# PixiFlood_SMT.net
KiCad netlist of a schematic drawn in EAGLE
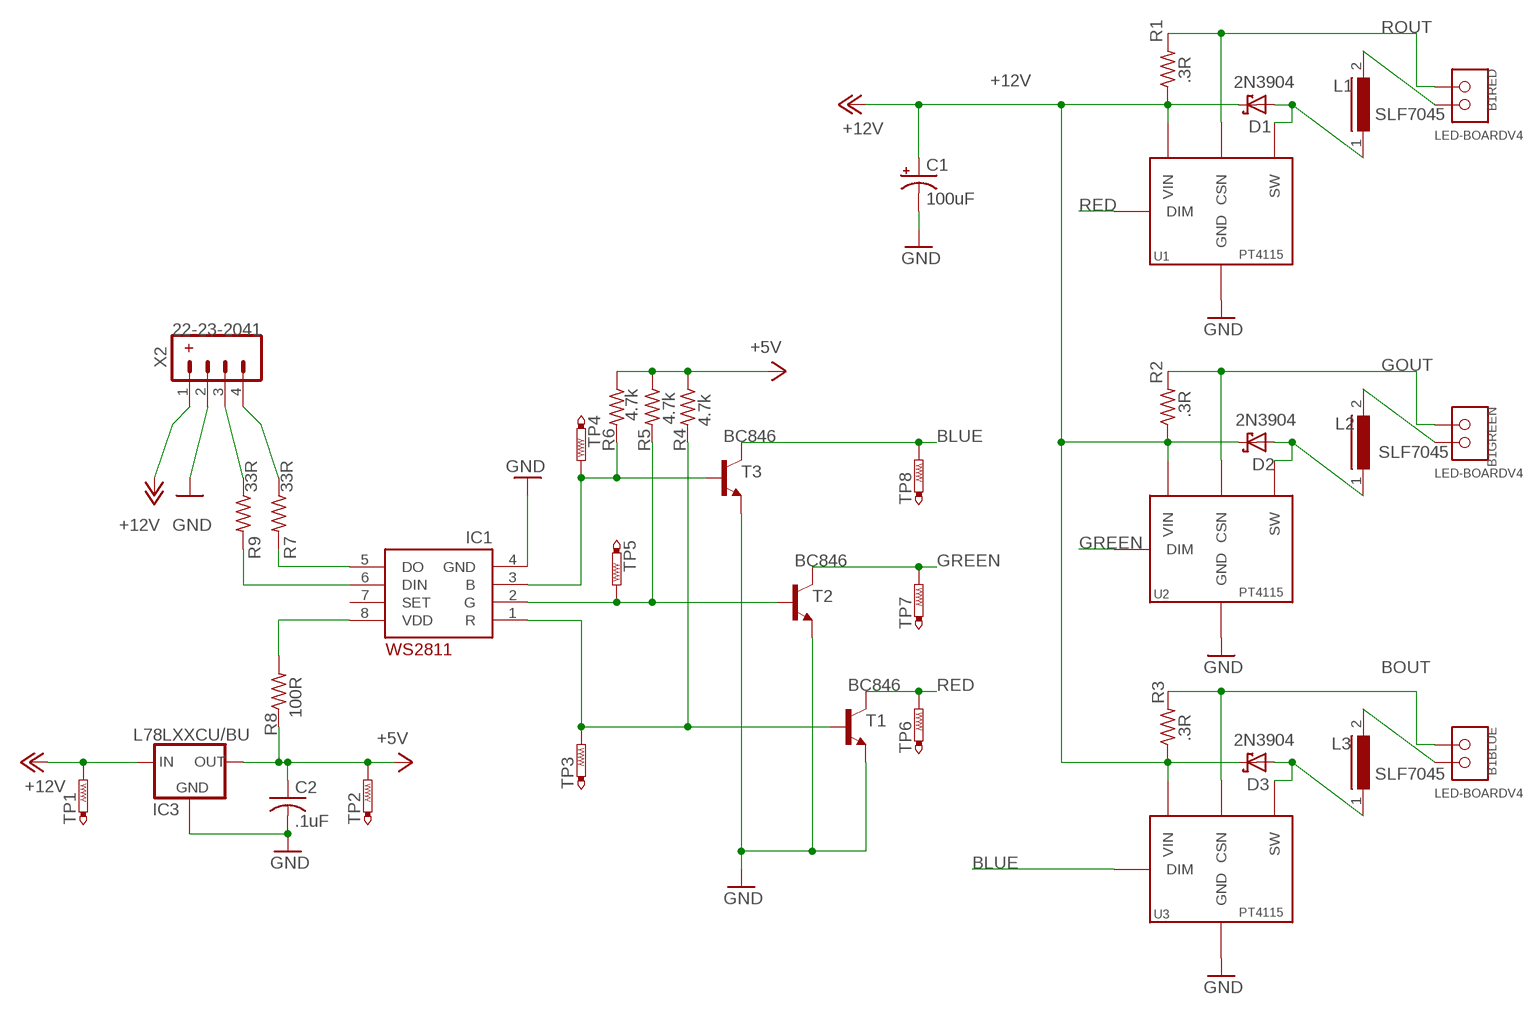
[diagram p0: schematic, sheet 1]

(export (version "E")
  (design (tool "Eeschema 10.0.6"))
  (components
    (comp (ref "B1")
      (value "LED-BOARDV4")
      (footprint "eagle-import:LED_BOARD-V4")
      (libsource (lib "eagle-import") (part "LED-BOARDV4"))
    )
    (comp (ref "C1")
      (value "100uF")
      (footprint "eagle-import:TT2D6L")
      (libsource (lib "eagle-import") (part "CPOL-USTT2D6L"))
    )
    (comp (ref "C2")
      (value ".1uF")
      (footprint "eagle-import:C0805")
      (libsource (lib "eagle-import") (part "C-USC0805"))
    )
    (comp (ref "D1")
      (value "2N3904")
      (footprint "eagle-import:SMA-DO214AC")
      (libsource (lib "eagle-import") (part "SCHOTTKY-DIODESS16"))
    )
    (comp (ref "D2")
      (value "2N3904")
      (footprint "eagle-import:SMA-DO214AC")
      (libsource (lib "eagle-import") (part "SCHOTTKY-DIODESS16"))
    )
    (comp (ref "D3")
      (value "2N3904")
      (footprint "eagle-import:SMA-DO214AC")
      (libsource (lib "eagle-import") (part "SCHOTTKY-DIODESS16"))
    )
    (comp (ref "IC1")
      (value "WS2811-SOP8")
      (footprint "eagle-import:SO08-SKINNYPADS")
      (libsource (lib "eagle-import") (part "WS2811-SOP8"))
    )
    (comp (ref "IC3")
      (value "L78LXXCU/BU")
      (footprint "eagle-import:SOT89")
      (libsource (lib "eagle-import") (part "L78LXXCU/BU"))
    )
    (comp (ref "L1")
      (value "SLF7045")
      (footprint "eagle-import:SLF7045")
      (libsource (lib "eagle-import") (part "SLF7045"))
    )
    (comp (ref "L2")
      (value "SLF7045")
      (footprint "eagle-import:SLF7045")
      (libsource (lib "eagle-import") (part "SLF7045"))
    )
    (comp (ref "L3")
      (value "SLF7045")
      (footprint "eagle-import:SLF7045")
      (libsource (lib "eagle-import") (part "SLF7045"))
    )
    (comp (ref "R1")
      (value ".3R")
      (footprint "eagle-import:R1206")
      (libsource (lib "eagle-import") (part "resistor_R-US_R1206"))
    )
    (comp (ref "R2")
      (value ".3R")
      (footprint "eagle-import:R1206")
      (libsource (lib "eagle-import") (part "resistor_R-US_R1206"))
    )
    (comp (ref "R3")
      (value ".3R")
      (footprint "eagle-import:R1206")
      (libsource (lib "eagle-import") (part "resistor_R-US_R1206"))
    )
    (comp (ref "R4")
      (value "4.7k")
      (footprint "eagle-import:R0805")
      (libsource (lib "eagle-import") (part "resistor_R-US_R0805"))
    )
    (comp (ref "R5")
      (value "4.7k")
      (footprint "eagle-import:R0805")
      (libsource (lib "eagle-import") (part "resistor_R-US_R0805"))
    )
    (comp (ref "R6")
      (value "4.7k")
      (footprint "eagle-import:R0805")
      (libsource (lib "eagle-import") (part "resistor_R-US_R0805"))
    )
    (comp (ref "R7")
      (value "33R")
      (footprint "eagle-import:M0805")
      (libsource (lib "eagle-import") (part "R-US_M0805"))
    )
    (comp (ref "R8")
      (value "100R")
      (footprint "eagle-import:R0805")
      (libsource (lib "eagle-import") (part "R-US_R0805"))
    )
    (comp (ref "R9")
      (value "33R")
      (footprint "eagle-import:R0805")
      (libsource (lib "eagle-import") (part "R-US_R0805"))
    )
    (comp (ref "T1")
      (value "BC846")
      (footprint "eagle-import:SOT23")
      (libsource (lib "eagle-import") (part "BC846"))
    )
    (comp (ref "T2")
      (value "BC846")
      (footprint "eagle-import:SOT23")
      (libsource (lib "eagle-import") (part "BC846"))
    )
    (comp (ref "T3")
      (value "BC846")
      (footprint "eagle-import:SOT23")
      (libsource (lib "eagle-import") (part "BC846"))
    )
    (comp (ref "TP1")
      (value "PTR1TP20SQ")
      (footprint "eagle-import:TP20SQ")
      (libsource (lib "eagle-import") (part "PTR1TP20SQ"))
    )
    (comp (ref "TP2")
      (value "PTR1TP20R")
      (footprint "eagle-import:TP20R")
      (libsource (lib "eagle-import") (part "PTR1TP20R"))
    )
    (comp (ref "TP3")
      (value "PTR1B1,27")
      (footprint "eagle-import:B1,27")
      (libsource (lib "eagle-import") (part "PTR1B1,27"))
    )
    (comp (ref "TP4")
      (value "PTR1B1,27")
      (footprint "eagle-import:B1,27")
      (libsource (lib "eagle-import") (part "PTR1B1,27"))
    )
    (comp (ref "TP5")
      (value "PTR1B1,27")
      (footprint "eagle-import:B1,27")
      (libsource (lib "eagle-import") (part "PTR1B1,27"))
    )
    (comp (ref "TP6")
      (value "PTR1B1,27")
      (footprint "eagle-import:B1,27")
      (libsource (lib "eagle-import") (part "PTR1B1,27"))
    )
    (comp (ref "TP7")
      (value "PTR1B1,27")
      (footprint "eagle-import:B1,27")
      (libsource (lib "eagle-import") (part "PTR1B1,27"))
    )
    (comp (ref "TP8")
      (value "PTR1B1,27")
      (footprint "eagle-import:B1,27")
      (libsource (lib "eagle-import") (part "PTR1B1,27"))
    )
    (comp (ref "U1")
      (value "PT4115B89E")
      (footprint "eagle-import:SOT89-5")
      (libsource (lib "eagle-import") (part "PT4115B89E"))
    )
    (comp (ref "U2")
      (value "PT4115B89E")
      (footprint "eagle-import:SOT89-5")
      (libsource (lib "eagle-import") (part "PT4115B89E"))
    )
    (comp (ref "U3")
      (value "PT4115B89E")
      (footprint "eagle-import:SOT89-5")
      (libsource (lib "eagle-import") (part "PT4115B89E"))
    )
    (comp (ref "X2")
      (value "22-23-2041")
      (footprint "eagle-import:22-23-2041")
      (fields (field (name "MF") "MOLEX"))
      (libsource (lib "eagle-import") (part "22-23-2041"))
    )
  )
  (nets
    (net (code "1") (name "+5V") (class "Default")
      (node (ref "C2") (pin "1") (pinfunction "1_1") (pintype "passive"))
      (node (ref "IC3") (pin "1") (pinfunction "OUT_1") (pintype "passive"))
      (node (ref "R4") (pin "1") (pinfunction "1_1") (pintype "passive"))
      (node (ref "R5") (pin "1") (pinfunction "1_1") (pintype "passive"))
      (node (ref "R6") (pin "1") (pinfunction "1_1") (pintype "passive"))
      (node (ref "R8") (pin "1") (pinfunction "1_1") (pintype "passive"))
      (node (ref "TP2") (pin "TP") (pinfunction "TP_TP") (pintype "input"))
    )
    (net (code "2") (name "+12V") (class "Default")
      (node (ref "C1") (pin "+") (pinfunction "+_+") (pintype "passive"))
      (node (ref "D1") (pin "K") (pinfunction "C_K") (pintype "passive"))
      (node (ref "D2") (pin "K") (pinfunction "C_K") (pintype "passive"))
      (node (ref "D3") (pin "K") (pinfunction "C_K") (pintype "passive"))
      (node (ref "IC3") (pin "3") (pinfunction "IN_3") (pintype "input"))
      (node (ref "R1") (pin "1") (pinfunction "1_1") (pintype "passive"))
      (node (ref "R2") (pin "1") (pinfunction "1_1") (pintype "passive"))
      (node (ref "R3") (pin "1") (pinfunction "1_1") (pintype "passive"))
      (node (ref "TP1") (pin "TP") (pinfunction "TP_TP") (pintype "input"))
      (node (ref "U1") (pin "5") (pinfunction "VIN_5") (pintype "power_in"))
      (node (ref "U2") (pin "5") (pinfunction "VIN_5") (pintype "power_in"))
      (node (ref "U3") (pin "5") (pinfunction "VIN_5") (pintype "power_in"))
      (node (ref "X2") (pin "1") (pinfunction "1_1") (pintype "passive"))
    )
    (net (code "3") (name "/BLUE") (class "Default")
      (node (ref "T3") (pin "3") (pinfunction "C_3") (pintype "passive"))
      (node (ref "TP8") (pin "TP") (pinfunction "TP_TP") (pintype "input"))
      (node (ref "U3") (pin "3") (pinfunction "DIM_3") (pintype "bidirectional"))
    )
    (net (code "4") (name "/BOUT") (class "Default")
      (node (ref "B1") (pin "B+") (pinfunction "P$2_B+") (pintype "bidirectional"))
      (node (ref "B1") (pin "B+@2") (pinfunction "P$2_B+@2") (pintype "bidirectional"))
      (node (ref "R3") (pin "2") (pinfunction "2_2") (pintype "passive"))
      (node (ref "U3") (pin "4") (pinfunction "CSN_4") (pintype "bidirectional"))
    )
    (net (code "5") (name "/GOUT") (class "Default")
      (node (ref "B1") (pin "G+") (pinfunction "P$2_G+") (pintype "bidirectional"))
      (node (ref "B1") (pin "G+@1") (pinfunction "P$2_G+@1") (pintype "bidirectional"))
      (node (ref "R2") (pin "2") (pinfunction "2_2") (pintype "passive"))
      (node (ref "U2") (pin "4") (pinfunction "CSN_4") (pintype "bidirectional"))
    )
    (net (code "6") (name "/GREEN") (class "Default")
      (node (ref "T2") (pin "3") (pinfunction "C_3") (pintype "passive"))
      (node (ref "TP7") (pin "TP") (pinfunction "TP_TP") (pintype "input"))
      (node (ref "U2") (pin "3") (pinfunction "DIM_3") (pintype "bidirectional"))
    )
    (net (code "7") (name "/RED") (class "Default")
      (node (ref "T1") (pin "3") (pinfunction "C_3") (pintype "passive"))
      (node (ref "TP6") (pin "TP") (pinfunction "TP_TP") (pintype "input"))
      (node (ref "U1") (pin "3") (pinfunction "DIM_3") (pintype "bidirectional"))
    )
    (net (code "8") (name "/ROUT") (class "Default")
      (node (ref "B1") (pin "R+") (pinfunction "P$2_R+") (pintype "bidirectional"))
      (node (ref "B1") (pin "R+@1") (pinfunction "P$2_R+@1") (pintype "bidirectional"))
      (node (ref "R1") (pin "2") (pinfunction "2_2") (pintype "passive"))
      (node (ref "U1") (pin "4") (pinfunction "CSN_4") (pintype "bidirectional"))
    )
    (net (code "9") (name "GND") (class "Default")
      (node (ref "C1") (pin "-") (pinfunction "-_-") (pintype "passive"))
      (node (ref "C2") (pin "2") (pinfunction "2_2") (pintype "passive"))
      (node (ref "IC1") (pin "4") (pinfunction "GND_4") (pintype "power_in"))
      (node (ref "IC3") (pin "4") (pinfunction "GND1_4") (pintype "input"))
      (node (ref "T1") (pin "2") (pinfunction "E_2") (pintype "passive"))
      (node (ref "T2") (pin "2") (pinfunction "E_2") (pintype "passive"))
      (node (ref "T3") (pin "2") (pinfunction "E_2") (pintype "passive"))
      (node (ref "U1") (pin "2") (pinfunction "GND_2") (pintype "power_in"))
      (node (ref "U1") (pin "2@1") (pinfunction "GND_2@1") (pintype "power_in"))
      (node (ref "U1") (pin "2@2") (pinfunction "GND_2@2") (pintype "power_in"))
      (node (ref "U1") (pin "2@3") (pinfunction "GND_2@3") (pintype "power_in"))
      (node (ref "U2") (pin "2") (pinfunction "GND_2") (pintype "power_in"))
      (node (ref "U2") (pin "2@1") (pinfunction "GND_2@1") (pintype "power_in"))
      (node (ref "U2") (pin "2@2") (pinfunction "GND_2@2") (pintype "power_in"))
      (node (ref "U2") (pin "2@3") (pinfunction "GND_2@3") (pintype "power_in"))
      (node (ref "U3") (pin "2") (pinfunction "GND_2") (pintype "power_in"))
      (node (ref "U3") (pin "2@1") (pinfunction "GND_2@1") (pintype "power_in"))
      (node (ref "U3") (pin "2@2") (pinfunction "GND_2@2") (pintype "power_in"))
      (node (ref "U3") (pin "2@3") (pinfunction "GND_2@3") (pintype "power_in"))
      (node (ref "X2") (pin "2") (pinfunction "2_2") (pintype "passive"))
    )
    (net (code "10") (name "Net-(B1A-P$1-PadB-)") (class "Default")
      (node (ref "B1") (pin "B-") (pinfunction "P$1_B-") (pintype "bidirectional"))
      (node (ref "B1") (pin "B-@1") (pinfunction "P$1_B-@1") (pintype "bidirectional"))
      (node (ref "L3") (pin "2") (pinfunction "2_2") (pintype "passive"))
    )
    (net (code "11") (name "Net-(B1B-P$1-PadG-)") (class "Default")
      (node (ref "B1") (pin "G-") (pinfunction "P$1_G-") (pintype "bidirectional"))
      (node (ref "B1") (pin "G-@1") (pinfunction "P$1_G-@1") (pintype "bidirectional"))
      (node (ref "L2") (pin "2") (pinfunction "2_2") (pintype "passive"))
    )
    (net (code "12") (name "Net-(B1C-P$1-PadR-)") (class "Default")
      (node (ref "B1") (pin "R-") (pinfunction "P$1_R-") (pintype "bidirectional"))
      (node (ref "B1") (pin "R-@1") (pinfunction "P$1_R-@1") (pintype "bidirectional"))
      (node (ref "L1") (pin "2") (pinfunction "2_2") (pintype "passive"))
    )
    (net (code "13") (name "Net-(IC1-B)") (class "Default")
      (node (ref "IC1") (pin "3") (pinfunction "B_3") (pintype "open_collector"))
      (node (ref "R6") (pin "2") (pinfunction "2_2") (pintype "passive"))
      (node (ref "T3") (pin "1") (pinfunction "B_1") (pintype "passive"))
      (node (ref "TP4") (pin "TP") (pinfunction "TP_TP") (pintype "input"))
    )
    (net (code "14") (name "Net-(IC1-DIN)") (class "Default")
      (node (ref "IC1") (pin "6") (pinfunction "DIN_6") (pintype "input"))
      (node (ref "R9") (pin "2") (pinfunction "2_2") (pintype "passive"))
    )
    (net (code "15") (name "Net-(IC1-DO)") (class "Default")
      (node (ref "IC1") (pin "5") (pinfunction "DO_5") (pintype "output"))
      (node (ref "R7") (pin "2") (pinfunction "2_2") (pintype "passive"))
    )
    (net (code "16") (name "Net-(IC1-G)") (class "Default")
      (node (ref "IC1") (pin "2") (pinfunction "G_2") (pintype "open_collector"))
      (node (ref "R5") (pin "2") (pinfunction "2_2") (pintype "passive"))
      (node (ref "T2") (pin "1") (pinfunction "B_1") (pintype "passive"))
      (node (ref "TP5") (pin "TP") (pinfunction "TP_TP") (pintype "input"))
    )
    (net (code "17") (name "Net-(IC1-R)") (class "Default")
      (node (ref "IC1") (pin "1") (pinfunction "R_1") (pintype "open_collector"))
      (node (ref "R4") (pin "2") (pinfunction "2_2") (pintype "passive"))
      (node (ref "T1") (pin "1") (pinfunction "B_1") (pintype "passive"))
      (node (ref "TP3") (pin "TP") (pinfunction "TP_TP") (pintype "input"))
    )
    (net (code "18") (name "Net-(IC1-VDD)") (class "Default")
      (node (ref "IC1") (pin "8") (pinfunction "VDD_8") (pintype "power_in"))
      (node (ref "R8") (pin "2") (pinfunction "2_2") (pintype "passive"))
    )
    (net (code "19") (name "Net-(R7-Pad1)") (class "Default")
      (node (ref "R7") (pin "1") (pinfunction "1_1") (pintype "passive"))
      (node (ref "X2") (pin "4") (pinfunction "4_4") (pintype "passive"))
    )
    (net (code "20") (name "Net-(R9-Pad1)") (class "Default")
      (node (ref "R9") (pin "1") (pinfunction "1_1") (pintype "passive"))
      (node (ref "X2") (pin "3") (pinfunction "3_3") (pintype "passive"))
    )
    (net (code "21") (name "Net-(U1-SW)") (class "Default")
      (node (ref "D1") (pin "A") (pinfunction "A_A") (pintype "passive"))
      (node (ref "L1") (pin "1") (pinfunction "1_1") (pintype "passive"))
      (node (ref "U1") (pin "1") (pinfunction "SW_1") (pintype "bidirectional"))
    )
    (net (code "22") (name "Net-(U2-SW)") (class "Default")
      (node (ref "D2") (pin "A") (pinfunction "A_A") (pintype "passive"))
      (node (ref "L2") (pin "1") (pinfunction "1_1") (pintype "passive"))
      (node (ref "U2") (pin "1") (pinfunction "SW_1") (pintype "bidirectional"))
    )
    (net (code "23") (name "Net-(U3-SW)") (class "Default")
      (node (ref "D3") (pin "A") (pinfunction "A_A") (pintype "passive"))
      (node (ref "L3") (pin "1") (pinfunction "1_1") (pintype "passive"))
      (node (ref "U3") (pin "1") (pinfunction "SW_1") (pintype "bidirectional"))
    )
    (net (code "24") (name "unconnected-(IC1-SET-Pad7)") (class "Default")
      (node (ref "IC1") (pin "7") (pinfunction "SET_7") (pintype "input"))
    )
    (net (code "25") (name "unconnected-(IC3-GND-Pad2)") (class "Default")
      (node (ref "IC3") (pin "2") (pinfunction "GND_2") (pintype "input"))
    )
  )
)
